# ShieldArduino_Due_5.net
KiCad netlist of a schematic drawn in Altium Designer
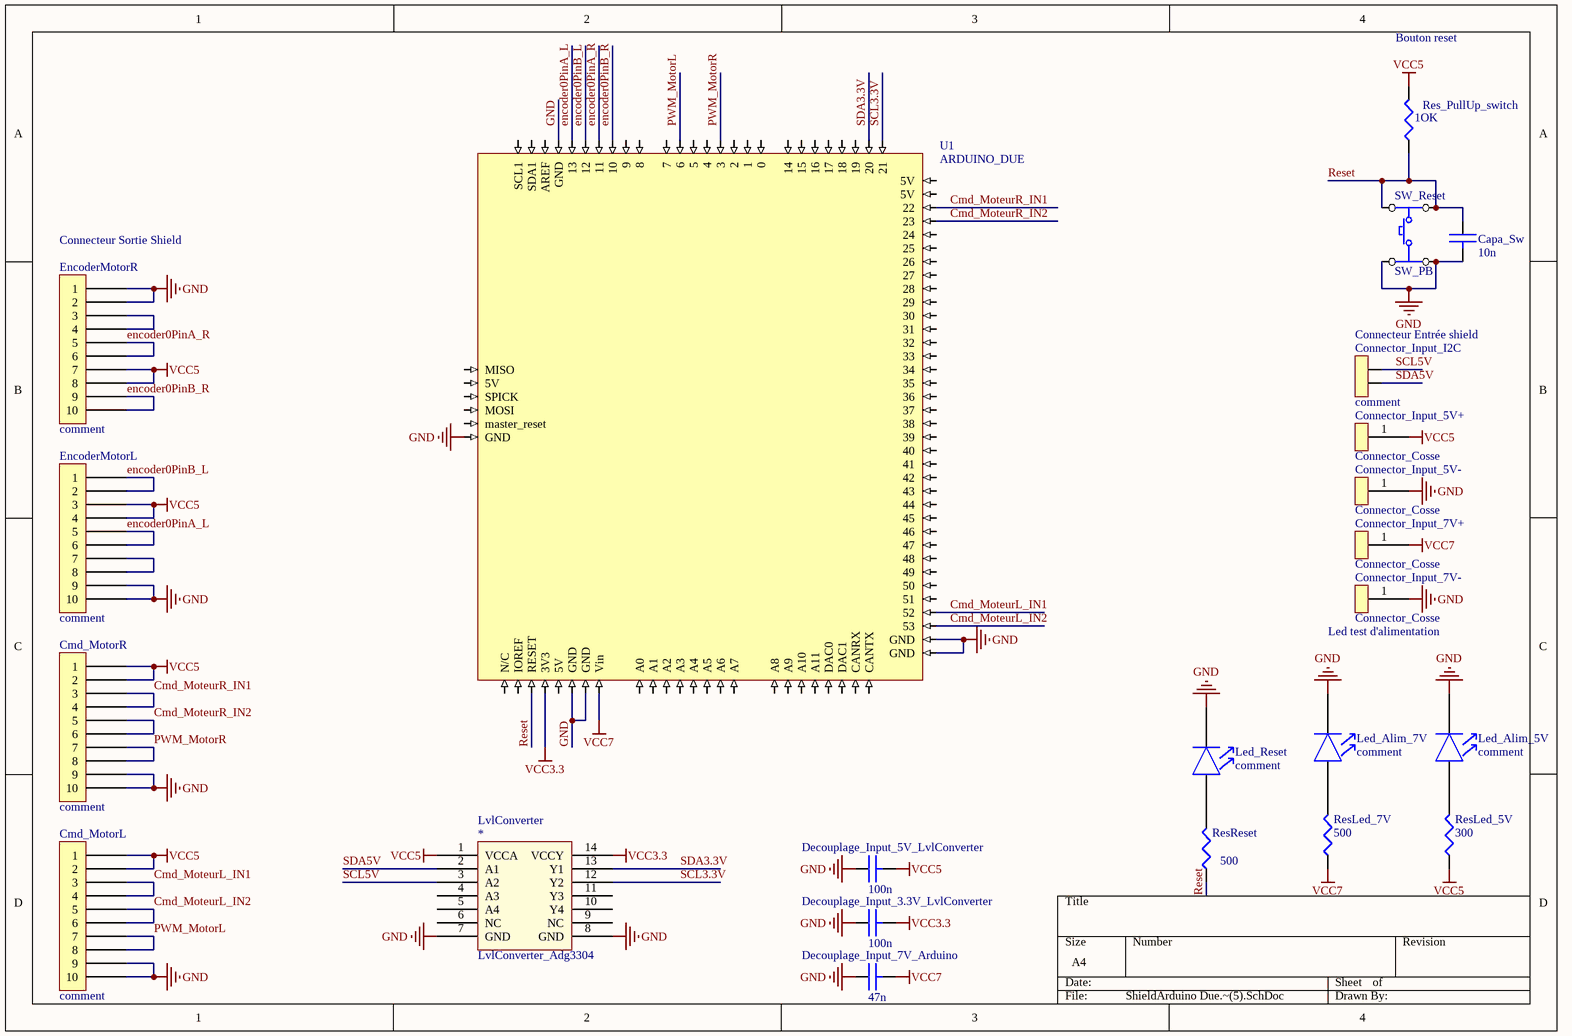
[diagram p0: ShieldArduino Due.~(5).SchDoc]

(export (version "E")
  (design (tool "Eeschema 10.0.6"))
  (components
    (comp (ref "*")
      (value "LvlConverter_Adg3304")
      (footprint "LvlConverter_Adg3304")
      (libsource (lib "LvlConverter_Adg3304") (part "LvlConverter_Adg3304"))
    )
    (comp (ref "Capa_Sw")
      (value "10n")
      (footprint "0805")
      (description "capacité non polarisée")
      (fields (field (name "Comment") "CAP"))
      (libsource (lib "ISEN_basics") (part "CAP"))
    )
    (comp (ref "Cmd_MotorL")
      (value "comment")
      (footprint "HE10-10V")
      (description "10-pin connector")
      (libsource (lib "ISEN_basics") (part "HE10-10"))
    )
    (comp (ref "Cmd_MotorR")
      (value "comment")
      (footprint "HE10-10V")
      (description "10-pin connector")
      (libsource (lib "ISEN_basics") (part "HE10-10"))
    )
    (comp (ref "Connector_Input_5V+")
      (value "Connector_Cosse")
      (footprint "Connector_Cosse")
      (libsource (lib "Connector_Cosse") (part "Connector_Cosse"))
    )
    (comp (ref "Connector_Input_5V-")
      (value "Connector_Cosse")
      (footprint "Connector_Cosse")
      (libsource (lib "Connector_Cosse") (part "Connector_Cosse"))
    )
    (comp (ref "Connector_Input_7V+")
      (value "Connector_Cosse")
      (footprint "Connector_Cosse")
      (libsource (lib "Connector_Cosse") (part "Connector_Cosse"))
    )
    (comp (ref "Connector_Input_7V-")
      (value "Connector_Cosse")
      (footprint "Connector_Cosse")
      (libsource (lib "Connector_Cosse") (part "Connector_Cosse"))
    )
    (comp (ref "Connector_Input_I2C")
      (value "comment")
      (footprint "AMP_2")
      (description "connecteur alim 2 pôles")
      (libsource (lib "ISEN_basics") (part "POWER2"))
    )
    (comp (ref "Decouplage_Input_3.3V_LvlConverter")
      (value "100n")
      (footprint "0805")
      (description "capacité non polarisée")
      (fields (field (name "Comment") "CAP"))
      (libsource (lib "ISEN_basics") (part "CAP"))
    )
    (comp (ref "Decouplage_Input_5V_LvlConverter")
      (value "100n")
      (footprint "0805")
      (description "capacité non polarisée")
      (fields (field (name "Comment") "CAP"))
      (libsource (lib "ISEN_basics") (part "CAP"))
    )
    (comp (ref "Decouplage_Input_7V_Arduino")
      (value "47n")
      (footprint "0805")
      (description "capacité non polarisée")
      (fields (field (name "Comment") "CAP"))
      (libsource (lib "ISEN_basics") (part "CAP"))
    )
    (comp (ref "EncoderMotorL")
      (value "comment")
      (footprint "HE10-10V")
      (description "10-pin connector")
      (libsource (lib "ISEN_basics") (part "HE10-10"))
    )
    (comp (ref "EncoderMotorR")
      (value "comment")
      (footprint "HE10-10V")
      (description "10-pin connector")
      (libsource (lib "ISEN_basics") (part "HE10-10"))
    )
    (comp (ref "Led_Alim_5V")
      (value "comment")
      (footprint "LED0805")
      (description "LED 5mm/3mm/CMS")
      (libsource (lib "ISEN_basics") (part "LED"))
    )
    (comp (ref "Led_Alim_7V")
      (value "comment")
      (footprint "LED0805")
      (description "LED 5mm/3mm/CMS")
      (libsource (lib "ISEN_basics") (part "LED"))
    )
    (comp (ref "Led_Reset")
      (value "comment")
      (footprint "LED0805")
      (description "LED 5mm/3mm/CMS")
      (libsource (lib "ISEN_basics") (part "LED"))
    )
    (comp (ref "ResLed_5V")
      (value "300")
      (footprint "0805")
      (description "resistance")
      (fields (field (name "Comment") "RES"))
      (libsource (lib "ISEN_basics") (part "RES"))
    )
    (comp (ref "ResLed_7V")
      (value "500")
      (footprint "0805")
      (description "resistance")
      (fields (field (name "Comment") "RES"))
      (libsource (lib "ISEN_basics") (part "RES"))
    )
    (comp (ref "ResReset")
      (value "500")
      (footprint "0805")
      (description "resistance")
      (fields (field (name "Comment") "RES"))
      (libsource (lib "ISEN_basics") (part "RES"))
    )
    (comp (ref "Res_PullUp_switch")
      (value "1OK")
      (footprint "0805")
      (description "resistance")
      (fields (field (name "Comment") "RES"))
      (libsource (lib "ISEN_basics") (part "RES"))
    )
    (comp (ref "SW_Reset") (value "SW_PB") (footprint "KSA") (libsource (lib "ISEN_basics") (part "SW_PB")))
    (comp (ref "U1")
      (value "ARDUINO_DUE")
      (footprint "ARDUINO_DUE")
      (libsource (lib "ISEN_basics") (part "ARDUINO_DUE"))
    )
  )
  (nets
    (net (code "1") (name "/Cmd_MoteurL_IN1") (class "Default")
      (node (ref "Cmd_MotorL") (pin "3") (pinfunction "3_3") (pintype "passive"))
      (node (ref "Cmd_MotorL") (pin "4") (pinfunction "4_4") (pintype "passive"))
      (node (ref "U1") (pin "59") (pinfunction "52_59") (pintype "input"))
    )
    (net (code "2") (name "/Cmd_MoteurL_IN2") (class "Default")
      (node (ref "Cmd_MotorL") (pin "5") (pinfunction "5_5") (pintype "passive"))
      (node (ref "Cmd_MotorL") (pin "6") (pinfunction "6_6") (pintype "passive"))
      (node (ref "U1") (pin "60") (pinfunction "53_60") (pintype "input"))
    )
    (net (code "3") (name "/Cmd_MoteurR_IN1") (class "Default")
      (node (ref "Cmd_MotorR") (pin "3") (pinfunction "3_3") (pintype "passive"))
      (node (ref "Cmd_MotorR") (pin "4") (pinfunction "4_4") (pintype "passive"))
      (node (ref "U1") (pin "29") (pinfunction "22_29") (pintype "input"))
    )
    (net (code "4") (name "/Cmd_MoteurR_IN2") (class "Default")
      (node (ref "Cmd_MotorR") (pin "5") (pinfunction "5_5") (pintype "passive"))
      (node (ref "Cmd_MotorR") (pin "6") (pinfunction "6_6") (pintype "passive"))
      (node (ref "U1") (pin "30") (pinfunction "23_30") (pintype "input"))
    )
    (net (code "5") (name "/PWM_MotorL") (class "Default")
      (node (ref "Cmd_MotorL") (pin "7") (pinfunction "7_7") (pintype "passive"))
      (node (ref "Cmd_MotorL") (pin "8") (pinfunction "8_8") (pintype "passive"))
      (node (ref "U1") (pin "12") (pinfunction "6_12") (pintype "input"))
    )
    (net (code "6") (name "/PWM_MotorR") (class "Default")
      (node (ref "Cmd_MotorR") (pin "7") (pinfunction "7_7") (pintype "passive"))
      (node (ref "Cmd_MotorR") (pin "8") (pinfunction "8_8") (pintype "passive"))
      (node (ref "U1") (pin "15") (pinfunction "3_15") (pintype "input"))
    )
    (net (code "7") (name "/Reset") (class "Default")
      (node (ref "Capa_Sw") (pin "1") (pinfunction "1_1") (pintype "passive"))
      (node (ref "ResReset") (pin "1") (pintype "passive"))
      (node (ref "Res_PullUp_switch") (pin "1") (pintype "passive"))
      (node (ref "SW_Reset") (pin "3") (pintype "passive"))
      (node (ref "SW_Reset") (pin "4") (pintype "passive"))
      (node (ref "U1") (pin "84") (pinfunction "RESET_84") (pintype "input"))
    )
    (net (code "8") (name "/SCL3.3V") (class "Default")
      (node (ref "*") (pin "12") (pinfunction "Y2_12") (pintype "power_in"))
      (node (ref "U1") (pin "26") (pinfunction "21_26") (pintype "input"))
    )
    (net (code "9") (name "/SCL5V") (class "Default")
      (node (ref "*") (pin "3") (pinfunction "A2_3") (pintype "power_in"))
      (node (ref "Connector_Input_I2C") (pin "1") (pintype "passive"))
    )
    (net (code "10") (name "/SDA3.3V") (class "Default")
      (node (ref "*") (pin "13") (pinfunction "Y1_13") (pintype "power_in"))
      (node (ref "U1") (pin "25") (pinfunction "20_25") (pintype "input"))
    )
    (net (code "11") (name "/SDA5V") (class "Default")
      (node (ref "*") (pin "2") (pinfunction "A1_2") (pintype "power_in"))
      (node (ref "Connector_Input_I2C") (pin "2") (pintype "passive"))
    )
    (net (code "12") (name "/encoder0PinA_L") (class "Default")
      (node (ref "EncoderMotorL") (pin "5") (pinfunction "5_5") (pintype "passive"))
      (node (ref "EncoderMotorL") (pin "6") (pinfunction "6_6") (pintype "passive"))
      (node (ref "U1") (pin "5") (pinfunction "13_5") (pintype "input"))
    )
    (net (code "13") (name "/encoder0PinA_R") (class "Default")
      (node (ref "EncoderMotorR") (pin "5") (pinfunction "5_5") (pintype "passive"))
      (node (ref "EncoderMotorR") (pin "6") (pinfunction "6_6") (pintype "passive"))
      (node (ref "U1") (pin "7") (pinfunction "11_7") (pintype "input"))
    )
    (net (code "14") (name "/encoder0PinB_L") (class "Default")
      (node (ref "EncoderMotorL") (pin "1") (pinfunction "1_1") (pintype "passive"))
      (node (ref "EncoderMotorL") (pin "2") (pinfunction "2_2") (pintype "passive"))
      (node (ref "U1") (pin "6") (pinfunction "12_6") (pintype "input"))
    )
    (net (code "15") (name "/encoder0PinB_R") (class "Default")
      (node (ref "EncoderMotorR") (pin "10") (pinfunction "10_10") (pintype "passive"))
      (node (ref "EncoderMotorR") (pin "9") (pinfunction "9_9") (pintype "passive"))
      (node (ref "U1") (pin "8") (pinfunction "10_8") (pintype "input"))
    )
    (net (code "16") (name "GND") (class "Default")
      (node (ref "*") (pin "7") (pinfunction "GND_7") (pintype "power_in"))
      (node (ref "*") (pin "8") (pinfunction "GND_8") (pintype "power_in"))
      (node (ref "Capa_Sw") (pin "2") (pinfunction "2_2") (pintype "passive"))
      (node (ref "Cmd_MotorL") (pin "10") (pinfunction "10_10") (pintype "passive"))
      (node (ref "Cmd_MotorL") (pin "9") (pinfunction "9_9") (pintype "passive"))
      (node (ref "Cmd_MotorR") (pin "10") (pinfunction "10_10") (pintype "passive"))
      (node (ref "Cmd_MotorR") (pin "9") (pinfunction "9_9") (pintype "passive"))
      (node (ref "Connector_Input_5V-") (pin "1") (pintype "passive"))
      (node (ref "Connector_Input_7V-") (pin "1") (pintype "passive"))
      (node (ref "Decouplage_Input_3.3V_LvlConverter") (pin "1") (pinfunction "1_1") (pintype "passive"))
      (node (ref "Decouplage_Input_5V_LvlConverter") (pin "1") (pinfunction "1_1") (pintype "passive"))
      (node (ref "Decouplage_Input_7V_Arduino") (pin "1") (pinfunction "1_1") (pintype "passive"))
      (node (ref "EncoderMotorL") (pin "10") (pinfunction "10_10") (pintype "passive"))
      (node (ref "EncoderMotorL") (pin "9") (pinfunction "9_9") (pintype "passive"))
      (node (ref "EncoderMotorR") (pin "1") (pinfunction "1_1") (pintype "passive"))
      (node (ref "EncoderMotorR") (pin "2") (pinfunction "2_2") (pintype "passive"))
      (node (ref "Led_Alim_5V") (pin "K") (pinfunction "10_K") (pintype "passive"))
      (node (ref "Led_Alim_7V") (pin "K") (pinfunction "10_K") (pintype "passive"))
      (node (ref "Led_Reset") (pin "K") (pinfunction "10_K") (pintype "passive"))
      (node (ref "SW_Reset") (pin "1") (pintype "passive"))
      (node (ref "SW_Reset") (pin "2") (pintype "passive"))
      (node (ref "U1") (pin "4") (pinfunction "GND_4") (pintype "input"))
      (node (ref "U1") (pin "61") (pinfunction "GND_61") (pintype "input"))
      (node (ref "U1") (pin "62") (pinfunction "GND_62") (pintype "input"))
      (node (ref "U1") (pin "80") (pinfunction "GND_80") (pintype "input"))
      (node (ref "U1") (pin "81") (pinfunction "GND_81") (pintype "input"))
      (node (ref "U1") (pin "92") (pinfunction "GND_92") (pintype "input"))
    )
    (net (code "17") (name "Net-(EncoderMotorL-Pad7)") (class "Default")
      (node (ref "EncoderMotorL") (pin "7") (pinfunction "7_7") (pintype "passive"))
      (node (ref "EncoderMotorL") (pin "8") (pinfunction "8_8") (pintype "passive"))
    )
    (net (code "18") (name "Net-(EncoderMotorR-Pad3)") (class "Default")
      (node (ref "EncoderMotorR") (pin "3") (pinfunction "3_3") (pintype "passive"))
      (node (ref "EncoderMotorR") (pin "4") (pinfunction "4_4") (pintype "passive"))
    )
    (net (code "19") (name "Net-(Led_Alim_5V-8)") (class "Default")
      (node (ref "Led_Alim_5V") (pin "A") (pinfunction "8_A") (pintype "passive"))
      (node (ref "ResLed_5V") (pin "2") (pintype "passive"))
    )
    (net (code "20") (name "Net-(Led_Alim_7V-8)") (class "Default")
      (node (ref "Led_Alim_7V") (pin "A") (pinfunction "8_A") (pintype "passive"))
      (node (ref "ResLed_7V") (pin "2") (pintype "passive"))
    )
    (net (code "21") (name "Net-(Led_Reset-8)") (class "Default")
      (node (ref "Led_Reset") (pin "A") (pinfunction "8_A") (pintype "passive"))
      (node (ref "ResReset") (pin "2") (pintype "passive"))
    )
    (net (code "22") (name "VCC3.3") (class "Default")
      (node (ref "*") (pin "14") (pinfunction "VCCY_14") (pintype "power_in"))
      (node (ref "Decouplage_Input_3.3V_LvlConverter") (pin "2") (pinfunction "2_2") (pintype "passive"))
      (node (ref "U1") (pin "83") (pinfunction "3V3_83") (pintype "input"))
    )
    (net (code "23") (name "VCC5") (class "Default")
      (node (ref "*") (pin "1") (pinfunction "VCCA_1") (pintype "power_in"))
      (node (ref "Cmd_MotorL") (pin "1") (pinfunction "1_1") (pintype "passive"))
      (node (ref "Cmd_MotorL") (pin "2") (pinfunction "2_2") (pintype "passive"))
      (node (ref "Cmd_MotorR") (pin "1") (pinfunction "1_1") (pintype "passive"))
      (node (ref "Cmd_MotorR") (pin "2") (pinfunction "2_2") (pintype "passive"))
      (node (ref "Connector_Input_5V+") (pin "1") (pintype "passive"))
      (node (ref "Decouplage_Input_5V_LvlConverter") (pin "2") (pinfunction "2_2") (pintype "passive"))
      (node (ref "EncoderMotorL") (pin "3") (pinfunction "3_3") (pintype "passive"))
      (node (ref "EncoderMotorL") (pin "4") (pinfunction "4_4") (pintype "passive"))
      (node (ref "EncoderMotorR") (pin "7") (pinfunction "7_7") (pintype "passive"))
      (node (ref "EncoderMotorR") (pin "8") (pinfunction "8_8") (pintype "passive"))
      (node (ref "ResLed_5V") (pin "1") (pintype "passive"))
      (node (ref "Res_PullUp_switch") (pin "2") (pintype "passive"))
    )
    (net (code "24") (name "VCC7") (class "Default")
      (node (ref "Connector_Input_7V+") (pin "1") (pintype "passive"))
      (node (ref "Decouplage_Input_7V_Arduino") (pin "2") (pinfunction "2_2") (pintype "passive"))
      (node (ref "ResLed_7V") (pin "1") (pintype "passive"))
      (node (ref "U1") (pin "79") (pinfunction "Vin_79") (pintype "input"))
    )
    (net (code "25") (name "unconnected-(*-A3-Pad4)") (class "Default")
      (node (ref "*") (pin "4") (pinfunction "A3_4") (pintype "power_in"))
    )
    (net (code "26") (name "unconnected-(*-A4-Pad5)") (class "Default")
      (node (ref "*") (pin "5") (pinfunction "A4_5") (pintype "power_in"))
    )
    (net (code "27") (name "unconnected-(*-NC-Pad6)") (class "Default")
      (node (ref "*") (pin "6") (pinfunction "NC_6") (pintype "power_in"))
    )
    (net (code "28") (name "unconnected-(*-NC-Pad9)") (class "Default")
      (node (ref "*") (pin "9") (pinfunction "NC_9") (pintype "power_in"))
    )
    (net (code "29") (name "unconnected-(*-Y3-Pad11)") (class "Default")
      (node (ref "*") (pin "11") (pinfunction "Y3_11") (pintype "power_in"))
    )
    (net (code "30") (name "unconnected-(*-Y4-Pad10)") (class "Default")
      (node (ref "*") (pin "10") (pinfunction "Y4_10") (pintype "power_in"))
    )
    (net (code "31") (name "unconnected-(U1-0-Pad18)") (class "Default")
      (node (ref "U1") (pin "18") (pinfunction "0_18") (pintype "input"))
    )
    (net (code "32") (name "unconnected-(U1-1-Pad17)") (class "Default")
      (node (ref "U1") (pin "17") (pinfunction "1_17") (pintype "input"))
    )
    (net (code "33") (name "unconnected-(U1-2-Pad16)") (class "Default")
      (node (ref "U1") (pin "16") (pinfunction "2_16") (pintype "input"))
    )
    (net (code "34") (name "unconnected-(U1-4-Pad14)") (class "Default")
      (node (ref "U1") (pin "14") (pinfunction "4_14") (pintype "input"))
    )
    (net (code "35") (name "unconnected-(U1-5-Pad13)") (class "Default")
      (node (ref "U1") (pin "13") (pinfunction "5_13") (pintype "input"))
    )
    (net (code "36") (name "unconnected-(U1-5V-Pad27)") (class "Default")
      (node (ref "U1") (pin "27") (pinfunction "5V_27") (pintype "input"))
    )
    (net (code "37") (name "unconnected-(U1-5V-Pad28)") (class "Default")
      (node (ref "U1") (pin "28") (pinfunction "5V_28") (pintype "input"))
    )
    (net (code "38") (name "unconnected-(U1-5V-Pad82)") (class "Default")
      (node (ref "U1") (pin "82") (pinfunction "5V_82") (pintype "input"))
    )
    (net (code "39") (name "unconnected-(U1-5V-Pad88)") (class "Default")
      (node (ref "U1") (pin "88") (pinfunction "5V_88") (pintype "input"))
    )
    (net (code "40") (name "unconnected-(U1-7-Pad11)") (class "Default")
      (node (ref "U1") (pin "11") (pinfunction "7_11") (pintype "input"))
    )
    (net (code "41") (name "unconnected-(U1-8-Pad10)") (class "Default")
      (node (ref "U1") (pin "10") (pinfunction "8_10") (pintype "input"))
    )
    (net (code "42") (name "unconnected-(U1-14-Pad19)") (class "Default")
      (node (ref "U1") (pin "19") (pinfunction "14_19") (pintype "input"))
    )
    (net (code "43") (name "unconnected-(U1-15-Pad20)") (class "Default")
      (node (ref "U1") (pin "20") (pinfunction "15_20") (pintype "input"))
    )
    (net (code "44") (name "unconnected-(U1-16-Pad21)") (class "Default")
      (node (ref "U1") (pin "21") (pinfunction "16_21") (pintype "input"))
    )
    (net (code "45") (name "unconnected-(U1-17-Pad22)") (class "Default")
      (node (ref "U1") (pin "22") (pinfunction "17_22") (pintype "input"))
    )
    (net (code "46") (name "unconnected-(U1-18-Pad23)") (class "Default")
      (node (ref "U1") (pin "23") (pinfunction "18_23") (pintype "input"))
    )
    (net (code "47") (name "unconnected-(U1-19-Pad24)") (class "Default")
      (node (ref "U1") (pin "24") (pinfunction "19_24") (pintype "input"))
    )
    (net (code "48") (name "unconnected-(U1-24-Pad31)") (class "Default")
      (node (ref "U1") (pin "31") (pinfunction "24_31") (pintype "input"))
    )
    (net (code "49") (name "unconnected-(U1-25-Pad32)") (class "Default")
      (node (ref "U1") (pin "32") (pinfunction "25_32") (pintype "input"))
    )
    (net (code "50") (name "unconnected-(U1-26-Pad33)") (class "Default")
      (node (ref "U1") (pin "33") (pinfunction "26_33") (pintype "input"))
    )
    (net (code "51") (name "unconnected-(U1-27-Pad34)") (class "Default")
      (node (ref "U1") (pin "34") (pinfunction "27_34") (pintype "input"))
    )
    (net (code "52") (name "unconnected-(U1-28-Pad35)") (class "Default")
      (node (ref "U1") (pin "35") (pinfunction "28_35") (pintype "input"))
    )
    (net (code "53") (name "unconnected-(U1-29-Pad36)") (class "Default")
      (node (ref "U1") (pin "36") (pinfunction "29_36") (pintype "input"))
    )
    (net (code "54") (name "unconnected-(U1-30-Pad37)") (class "Default")
      (node (ref "U1") (pin "37") (pinfunction "30_37") (pintype "input"))
    )
    (net (code "55") (name "unconnected-(U1-31-Pad38)") (class "Default")
      (node (ref "U1") (pin "38") (pinfunction "31_38") (pintype "input"))
    )
    (net (code "56") (name "unconnected-(U1-32-Pad39)") (class "Default")
      (node (ref "U1") (pin "39") (pinfunction "32_39") (pintype "input"))
    )
    (net (code "57") (name "unconnected-(U1-33-Pad40)") (class "Default")
      (node (ref "U1") (pin "40") (pinfunction "33_40") (pintype "input"))
    )
    (net (code "58") (name "unconnected-(U1-34-Pad41)") (class "Default")
      (node (ref "U1") (pin "41") (pinfunction "34_41") (pintype "input"))
    )
    (net (code "59") (name "unconnected-(U1-35-Pad42)") (class "Default")
      (node (ref "U1") (pin "42") (pinfunction "35_42") (pintype "input"))
    )
    (net (code "60") (name "unconnected-(U1-36-Pad43)") (class "Default")
      (node (ref "U1") (pin "43") (pinfunction "36_43") (pintype "input"))
    )
    (net (code "61") (name "unconnected-(U1-37-Pad44)") (class "Default")
      (node (ref "U1") (pin "44") (pinfunction "37_44") (pintype "input"))
    )
    (net (code "62") (name "unconnected-(U1-38-Pad45)") (class "Default")
      (node (ref "U1") (pin "45") (pinfunction "38_45") (pintype "input"))
    )
    (net (code "63") (name "unconnected-(U1-39-Pad46)") (class "Default")
      (node (ref "U1") (pin "46") (pinfunction "39_46") (pintype "input"))
    )
    (net (code "64") (name "unconnected-(U1-40-Pad47)") (class "Default")
      (node (ref "U1") (pin "47") (pinfunction "40_47") (pintype "input"))
    )
    (net (code "65") (name "unconnected-(U1-41-Pad48)") (class "Default")
      (node (ref "U1") (pin "48") (pinfunction "41_48") (pintype "input"))
    )
    (net (code "66") (name "unconnected-(U1-42-Pad49)") (class "Default")
      (node (ref "U1") (pin "49") (pinfunction "42_49") (pintype "input"))
    )
    (net (code "67") (name "unconnected-(U1-43-Pad50)") (class "Default")
      (node (ref "U1") (pin "50") (pinfunction "43_50") (pintype "input"))
    )
    (net (code "68") (name "unconnected-(U1-44-Pad51)") (class "Default")
      (node (ref "U1") (pin "51") (pinfunction "44_51") (pintype "input"))
    )
    (net (code "69") (name "unconnected-(U1-45-Pad52)") (class "Default")
      (node (ref "U1") (pin "52") (pinfunction "45_52") (pintype "input"))
    )
    (net (code "70") (name "unconnected-(U1-46-Pad53)") (class "Default")
      (node (ref "U1") (pin "53") (pinfunction "46_53") (pintype "input"))
    )
    (net (code "71") (name "unconnected-(U1-47-Pad54)") (class "Default")
      (node (ref "U1") (pin "54") (pinfunction "47_54") (pintype "input"))
    )
    (net (code "72") (name "unconnected-(U1-48-Pad55)") (class "Default")
      (node (ref "U1") (pin "55") (pinfunction "48_55") (pintype "input"))
    )
    (net (code "73") (name "unconnected-(U1-49-Pad56)") (class "Default")
      (node (ref "U1") (pin "56") (pinfunction "49_56") (pintype "input"))
    )
    (net (code "74") (name "unconnected-(U1-50-Pad57)") (class "Default")
      (node (ref "U1") (pin "57") (pinfunction "50_57") (pintype "input"))
    )
    (net (code "75") (name "unconnected-(U1-51-Pad58)") (class "Default")
      (node (ref "U1") (pin "58") (pinfunction "51_58") (pintype "input"))
    )
    (net (code "76") (name "unconnected-(U1-A0-Pad78)") (class "Default")
      (node (ref "U1") (pin "78") (pinfunction "A0_78") (pintype "input"))
    )
    (net (code "77") (name "unconnected-(U1-A1-Pad77)") (class "Default")
      (node (ref "U1") (pin "77") (pinfunction "A1_77") (pintype "input"))
    )
    (net (code "78") (name "unconnected-(U1-A2-Pad76)") (class "Default")
      (node (ref "U1") (pin "76") (pinfunction "A2_76") (pintype "input"))
    )
    (net (code "79") (name "unconnected-(U1-A3-Pad75)") (class "Default")
      (node (ref "U1") (pin "75") (pinfunction "A3_75") (pintype "input"))
    )
    (net (code "80") (name "unconnected-(U1-A4-Pad74)") (class "Default")
      (node (ref "U1") (pin "74") (pinfunction "A4_74") (pintype "input"))
    )
    (net (code "81") (name "unconnected-(U1-A5-Pad73)") (class "Default")
      (node (ref "U1") (pin "73") (pinfunction "A5_73") (pintype "input"))
    )
    (net (code "82") (name "unconnected-(U1-A6-Pad72)") (class "Default")
      (node (ref "U1") (pin "72") (pinfunction "A6_72") (pintype "input"))
    )
    (net (code "83") (name "unconnected-(U1-A7-Pad71)") (class "Default")
      (node (ref "U1") (pin "71") (pinfunction "A7_71") (pintype "input"))
    )
    (net (code "84") (name "unconnected-(U1-A8-Pad70)") (class "Default")
      (node (ref "U1") (pin "70") (pinfunction "A8_70") (pintype "input"))
    )
    (net (code "85") (name "unconnected-(U1-A9-Pad69)") (class "Default")
      (node (ref "U1") (pin "69") (pinfunction "A9_69") (pintype "input"))
    )
    (net (code "86") (name "unconnected-(U1-A10-Pad68)") (class "Default")
      (node (ref "U1") (pin "68") (pinfunction "A10_68") (pintype "input"))
    )
    (net (code "87") (name "unconnected-(U1-A11-Pad67)") (class "Default")
      (node (ref "U1") (pin "67") (pinfunction "A11_67") (pintype "input"))
    )
    (net (code "88") (name "unconnected-(U1-AREF-Pad3)") (class "Default")
      (node (ref "U1") (pin "3") (pinfunction "AREF_3") (pintype "input"))
    )
    (net (code "89") (name "unconnected-(U1-CANRX-Pad64)") (class "Default")
      (node (ref "U1") (pin "64") (pinfunction "CANRX_64") (pintype "input"))
    )
    (net (code "90") (name "unconnected-(U1-CANTX-Pad63)") (class "Default")
      (node (ref "U1") (pin "63") (pinfunction "CANTX_63") (pintype "input"))
    )
    (net (code "91") (name "unconnected-(U1-DAC0-Pad66)") (class "Default")
      (node (ref "U1") (pin "66") (pinfunction "DAC0_66") (pintype "input"))
    )
    (net (code "92") (name "unconnected-(U1-DAC1-Pad65)") (class "Default")
      (node (ref "U1") (pin "65") (pinfunction "DAC1_65") (pintype "input"))
    )
    (net (code "93") (name "unconnected-(U1-IOREF-Pad85)") (class "Default")
      (node (ref "U1") (pin "85") (pinfunction "IOREF_85") (pintype "input"))
    )
    (net (code "94") (name "unconnected-(U1-MISO-Pad87)") (class "Default")
      (node (ref "U1") (pin "87") (pinfunction "MISO_87") (pintype "input"))
    )
    (net (code "95") (name "unconnected-(U1-MOSI-Pad90)") (class "Default")
      (node (ref "U1") (pin "90") (pinfunction "MOSI_90") (pintype "input"))
    )
    (net (code "96") (name "unconnected-(U1-N{slash}C-Pad86)") (class "Default")
      (node (ref "U1") (pin "86") (pinfunction "N/C_86") (pintype "input"))
    )
    (net (code "97") (name "unconnected-(U1-Pad9)") (class "Default")
      (node (ref "U1") (pin "9") (pinfunction "9_9") (pintype "input"))
    )
    (net (code "98") (name "unconnected-(U1-SCL1-Pad1)") (class "Default")
      (node (ref "U1") (pin "1") (pinfunction "SCL1_1") (pintype "input"))
    )
    (net (code "99") (name "unconnected-(U1-SDA1-Pad2)") (class "Default")
      (node (ref "U1") (pin "2") (pinfunction "SDA1_2") (pintype "input"))
    )
    (net (code "100") (name "unconnected-(U1-SPICK-Pad89)") (class "Default")
      (node (ref "U1") (pin "89") (pinfunction "SPICK_89") (pintype "input"))
    )
    (net (code "101") (name "unconnected-(U1-master_reset-Pad91)") (class "Default")
      (node (ref "U1") (pin "91") (pinfunction "master_reset_91") (pintype "input"))
    )
  )
)
